# PitchshiftDelay-dsPIC_v2_3.net
KiCad netlist of a schematic drawn in EAGLE
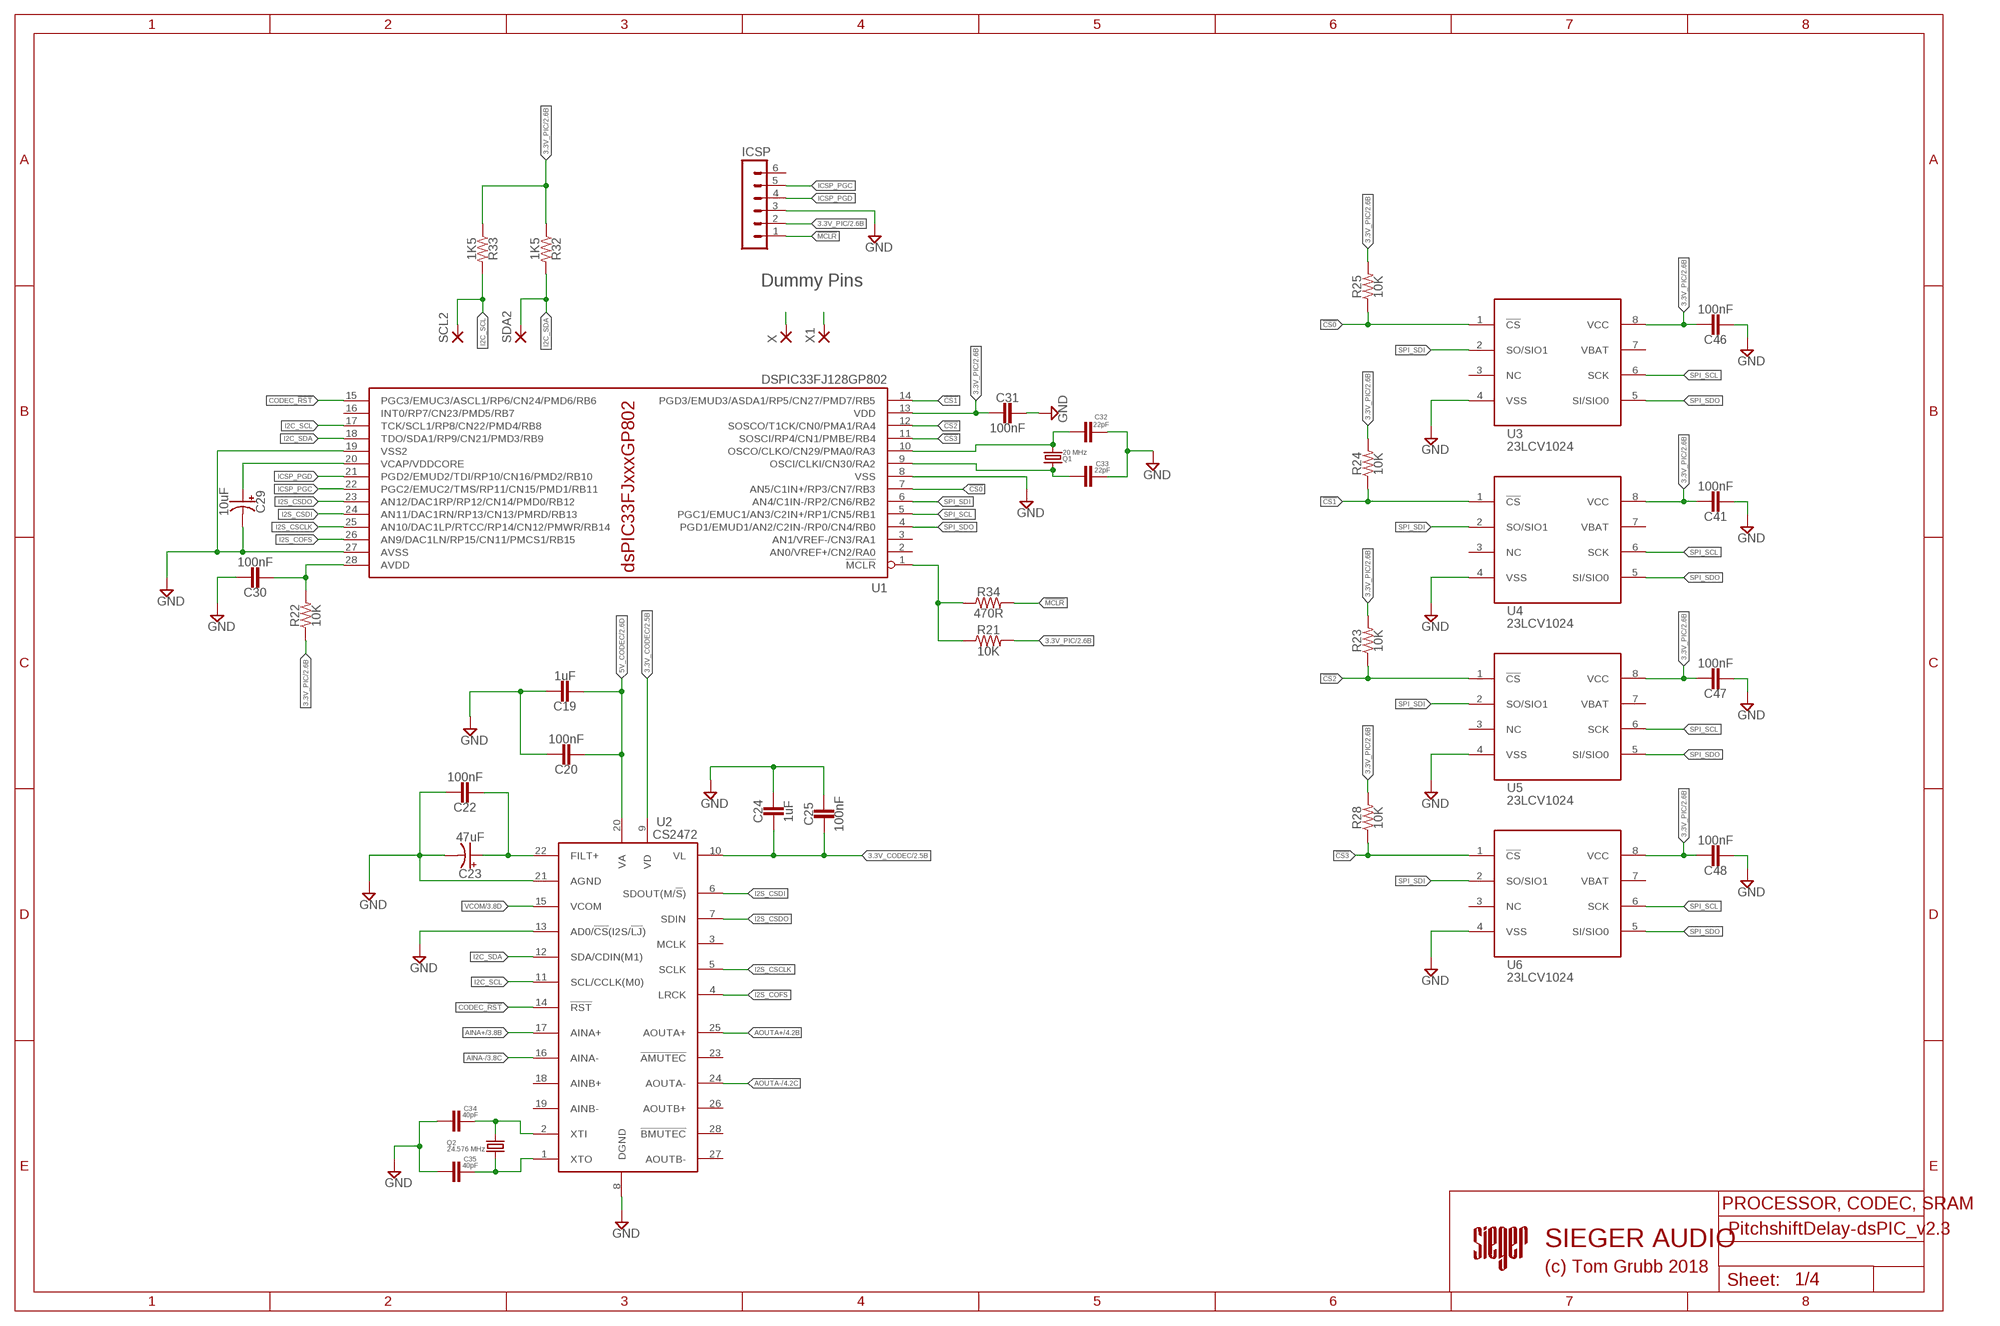
[diagram p0: schematic, sheet 1]
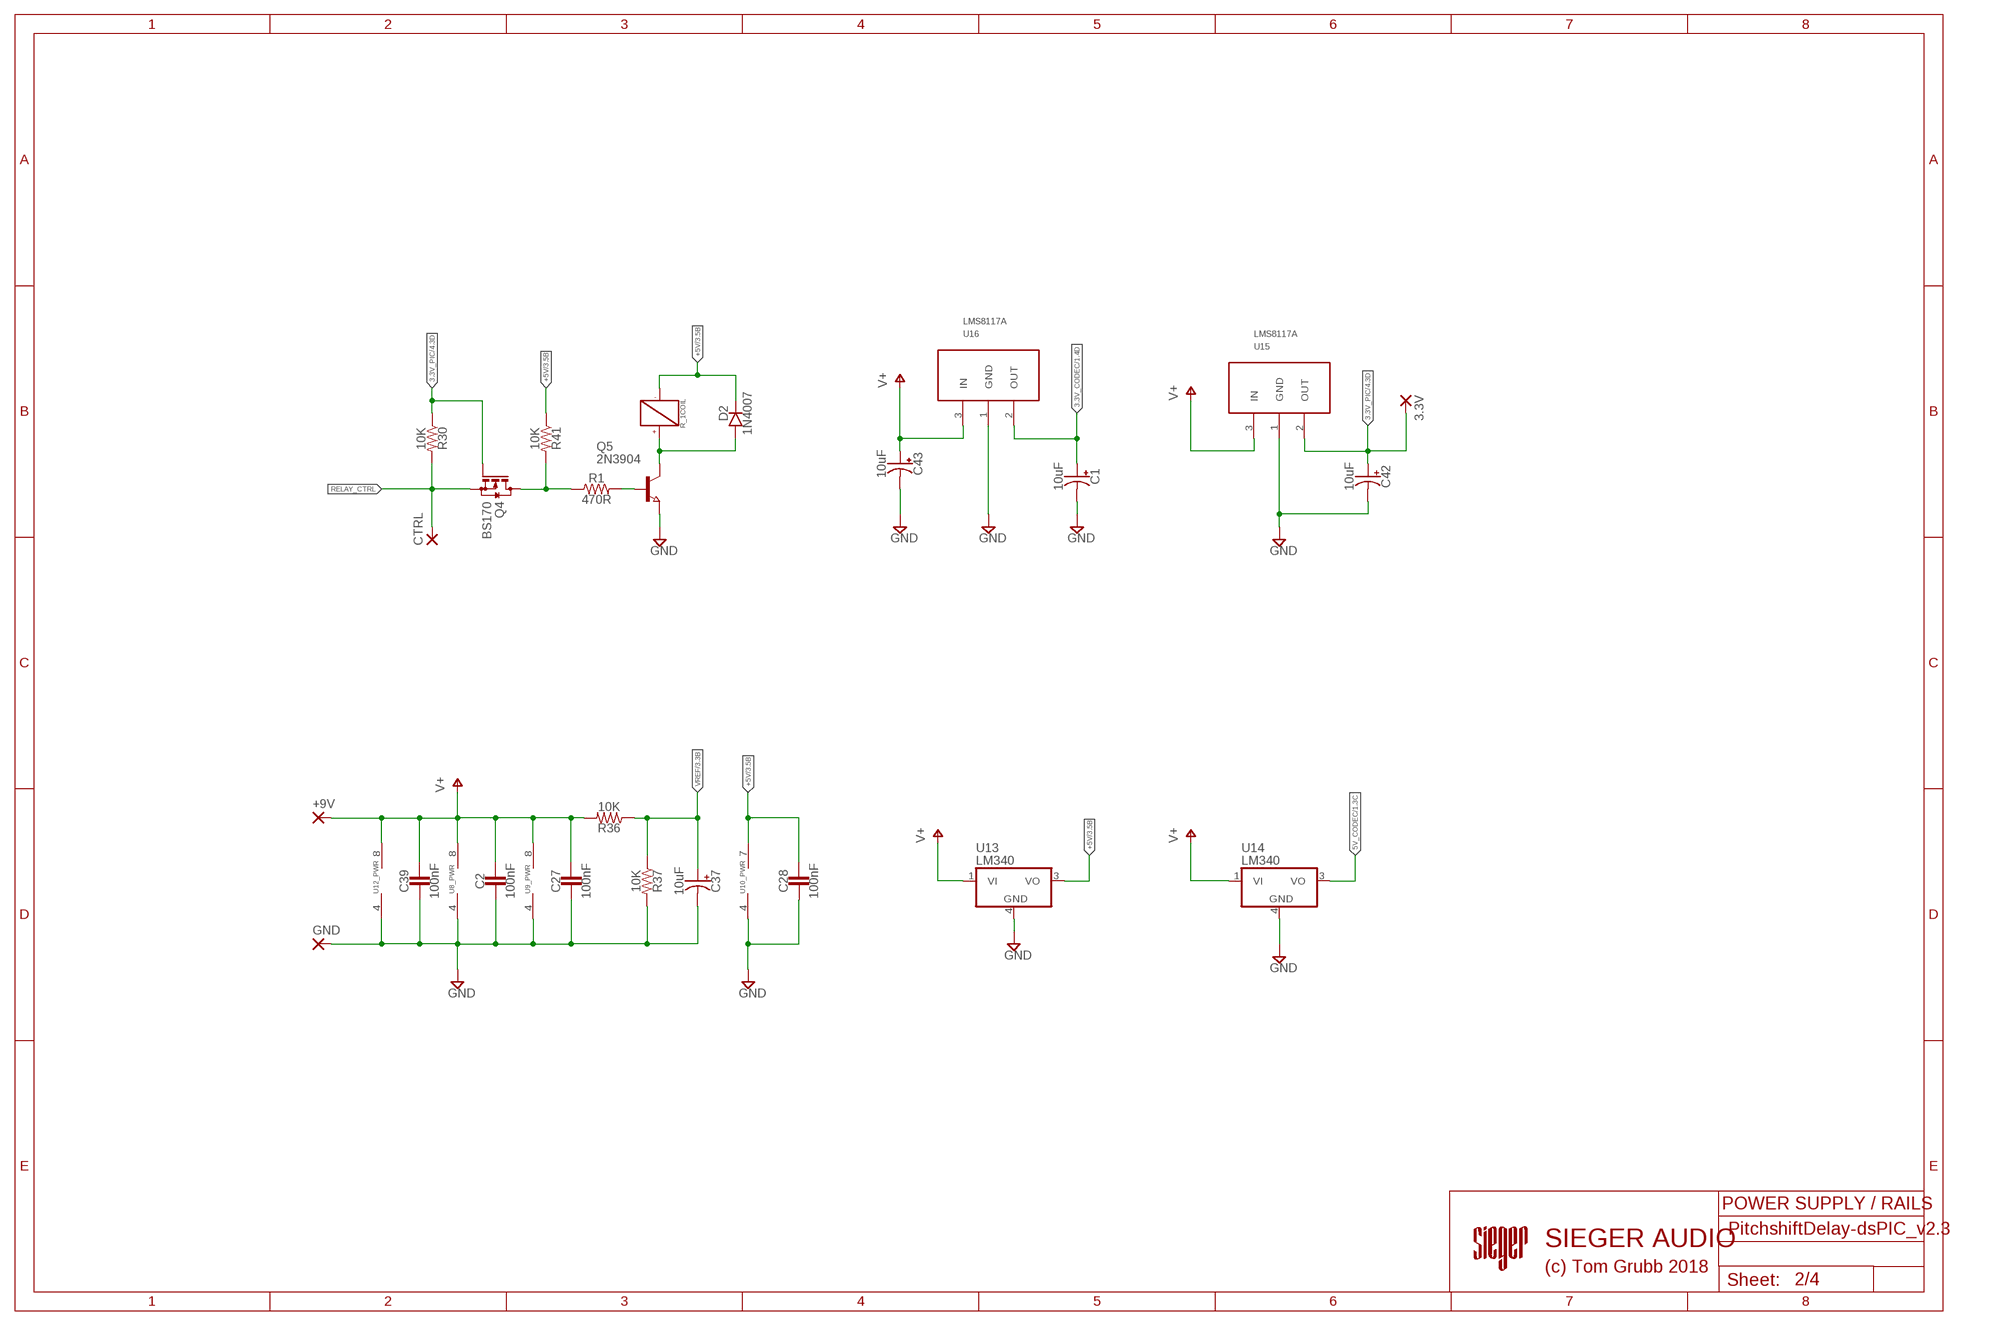
[diagram p1: schematic, sheet 2]
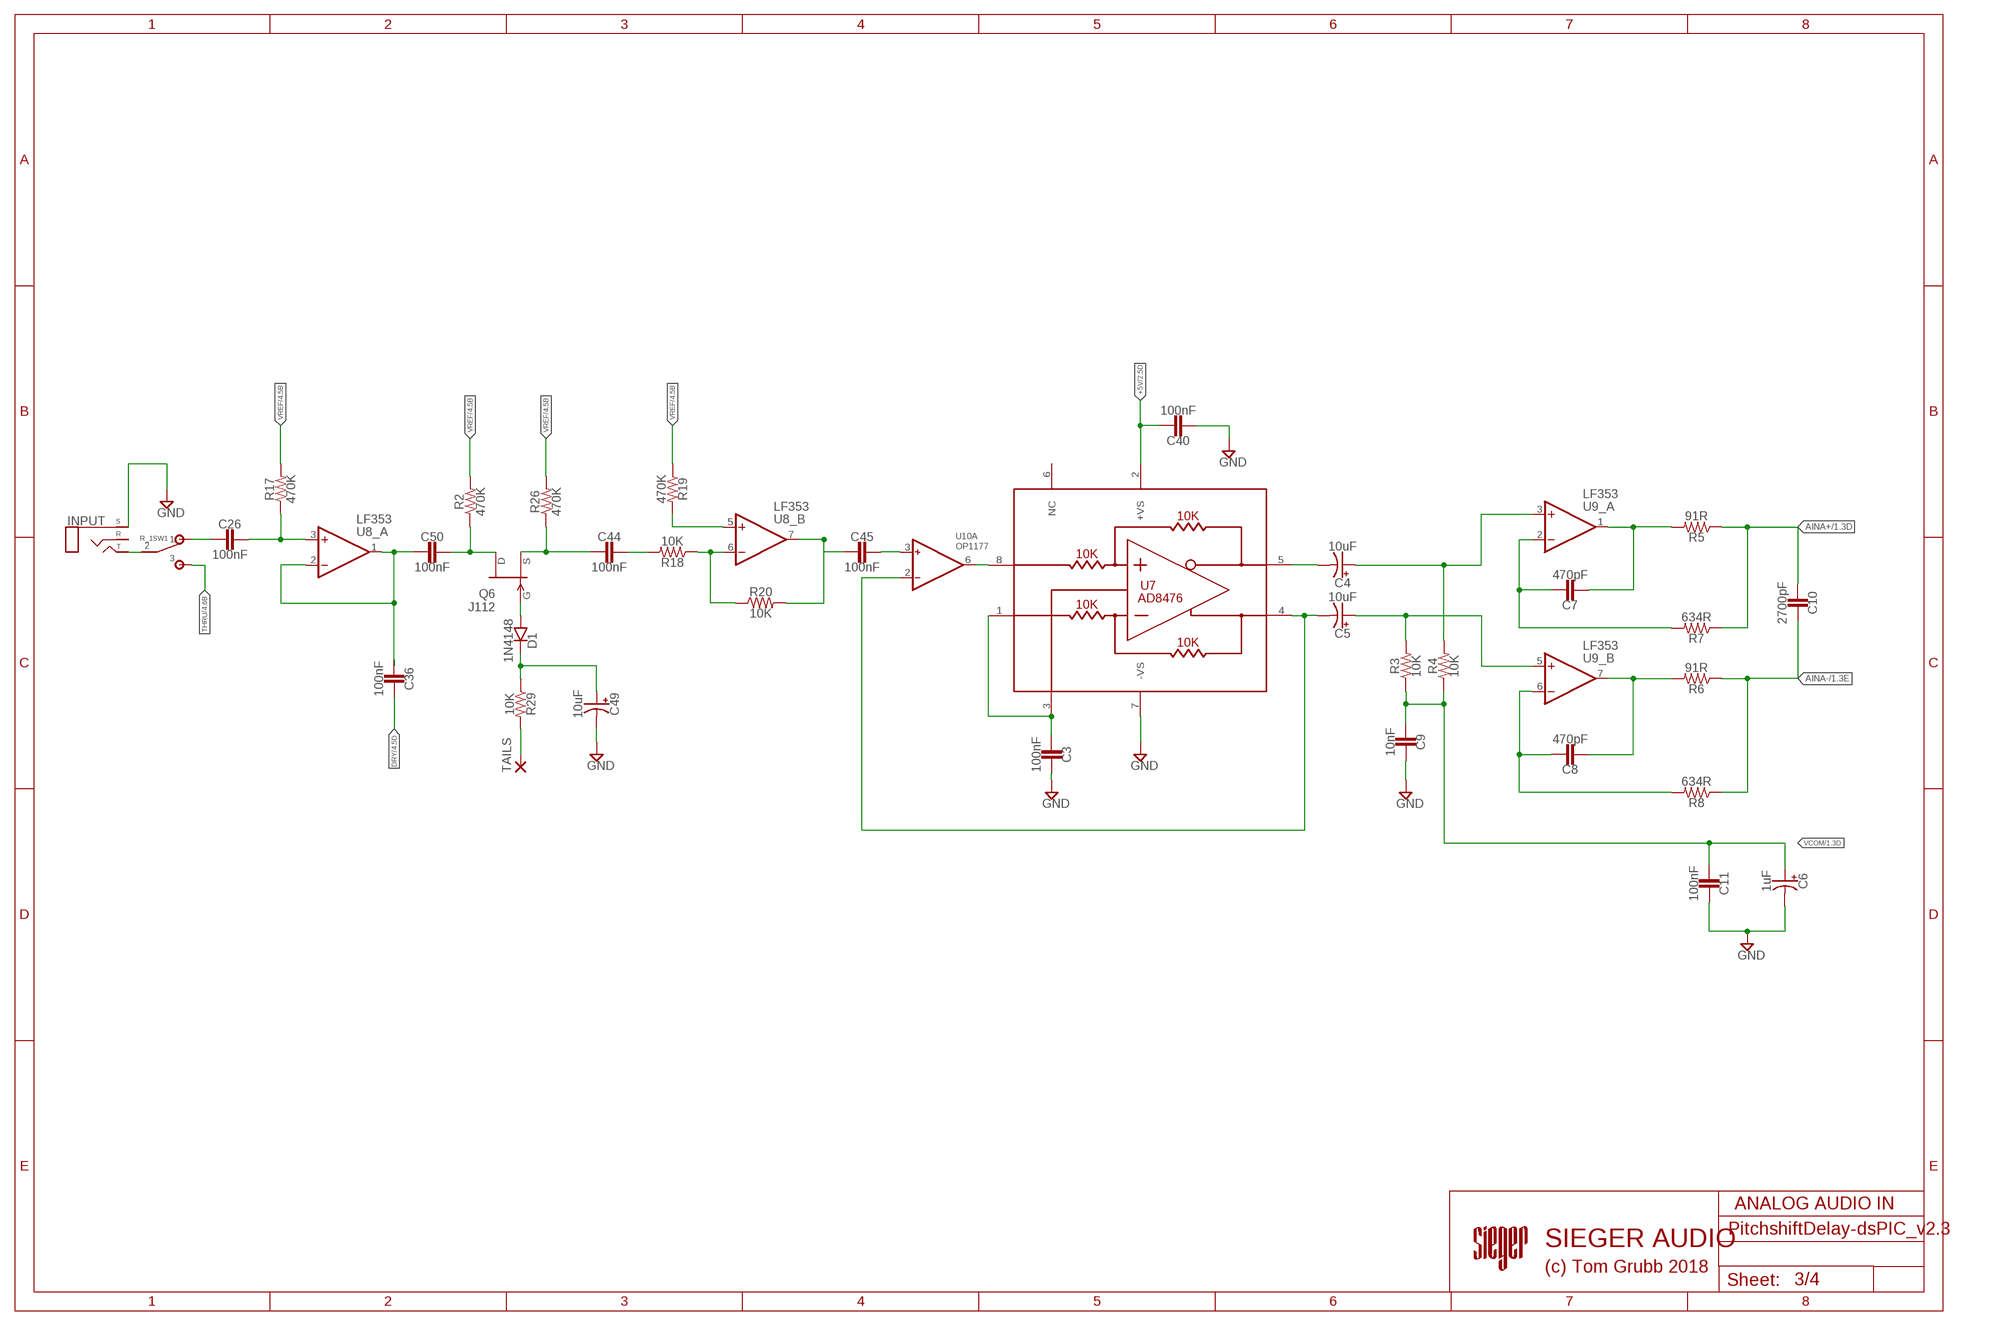
[diagram p2: schematic, sheet 3]
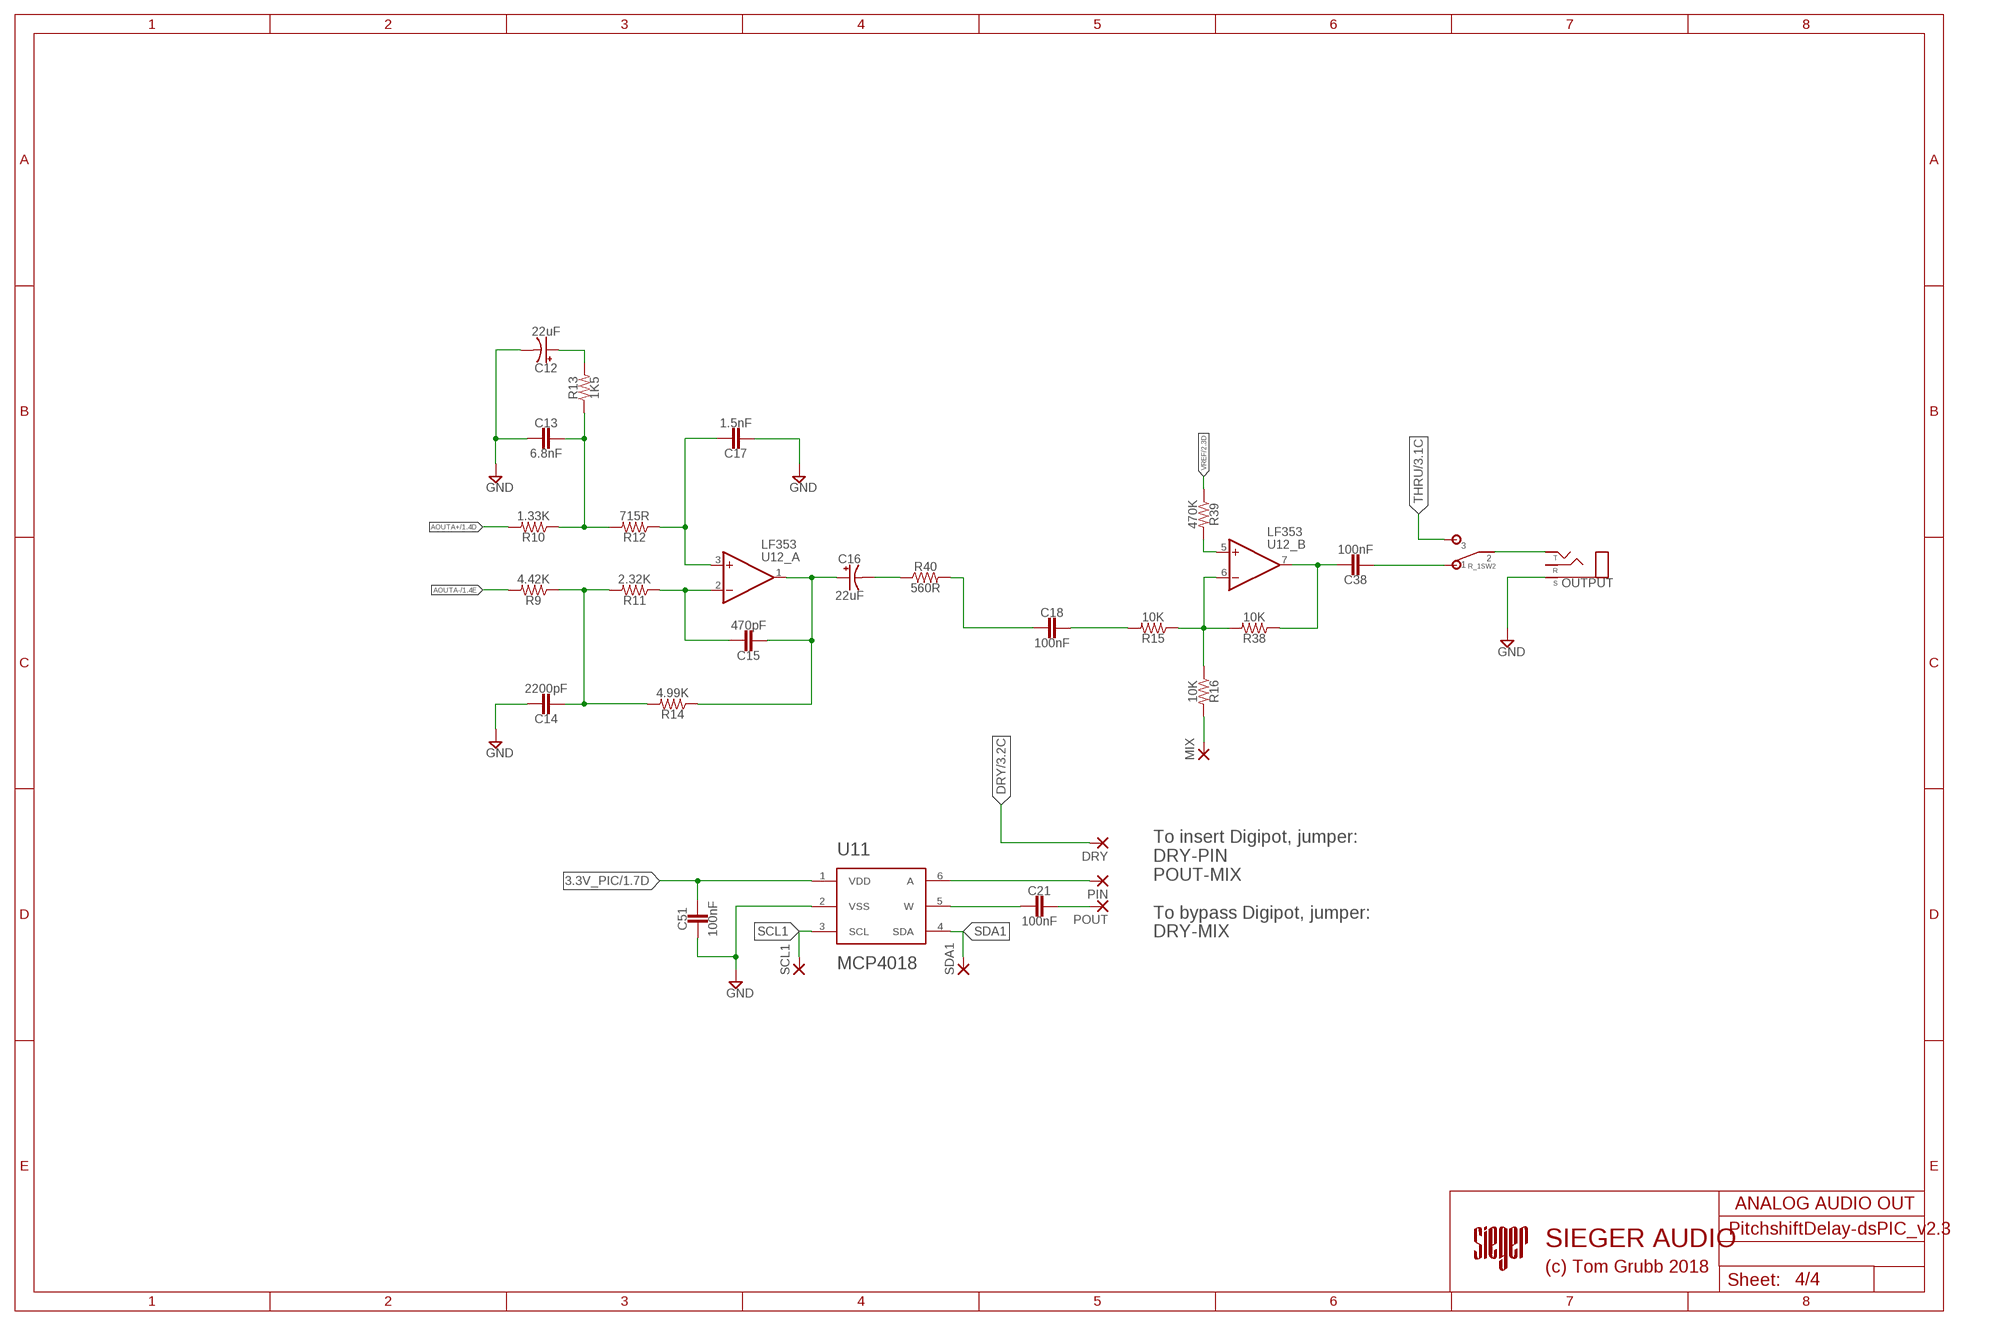
[diagram p3: schematic, sheet 4]

(export (version "E")
  (design (tool "Eeschema 10.0.6"))
  (components
    (comp (ref "C3")
      (value "100nF")
      (footprint "eagle-import:050X030_025")
      (libsource (lib "eagle-import") (part "CER/FILM1"))
    )
    (comp (ref "C4")
      (value "10uF")
      (footprint "eagle-import:050_020_1")
      (libsource (lib "eagle-import") (part "0501"))
    )
    (comp (ref "C5")
      (value "10uF")
      (footprint "eagle-import:050_020_1")
      (libsource (lib "eagle-import") (part "0501"))
    )
    (comp (ref "C6")
      (value "1uF")
      (footprint "eagle-import:050_020_1")
      (libsource (lib "eagle-import") (part "0501"))
    )
    (comp (ref "C7")
      (value "470pF")
      (footprint "eagle-import:BOX_SMALL")
      (libsource (lib "eagle-import") (part "CER/FILMBOX.1"))
    )
    (comp (ref "C8")
      (value "470pF")
      (footprint "eagle-import:BOX_SMALL")
      (libsource (lib "eagle-import") (part "CER/FILMBOX.1"))
    )
    (comp (ref "C9")
      (value "10nF")
      (footprint "eagle-import:050X030_025")
      (libsource (lib "eagle-import") (part "CER/FILM1"))
    )
    (comp (ref "C10")
      (value "2700pF")
      (footprint "eagle-import:BOX_SMALL")
      (libsource (lib "eagle-import") (part "CER/FILMBOX.1"))
    )
    (comp (ref "C11")
      (value "100nF")
      (footprint "eagle-import:050X030_025")
      (libsource (lib "eagle-import") (part "CER/FILM1"))
    )
    (comp (ref "C26")
      (value "100nF")
      (footprint "eagle-import:BOX_SMALL")
      (libsource (lib "eagle-import") (part "CER/FILMBOX.1"))
    )
    (comp (ref "C36")
      (value "100nF")
      (footprint "eagle-import:BOX_SMALL")
      (libsource (lib "eagle-import") (part "CER/FILMBOX.1"))
    )
    (comp (ref "C40")
      (value "100nF")
      (footprint "eagle-import:050X030_025")
      (libsource (lib "eagle-import") (part "CER/FILM1"))
    )
    (comp (ref "C44")
      (value "100nF")
      (footprint "eagle-import:BOX_SMALL")
      (libsource (lib "eagle-import") (part "CER/FILMBOX.1"))
    )
    (comp (ref "C45")
      (value "100nF")
      (footprint "eagle-import:BOX_SMALL")
      (libsource (lib "eagle-import") (part "CER/FILMBOX.1"))
    )
    (comp (ref "C49")
      (value "10uF")
      (footprint "eagle-import:050_020_1")
      (libsource (lib "eagle-import") (part "0501"))
    )
    (comp (ref "C50")
      (value "100nF")
      (footprint "eagle-import:BOX_SMALL")
      (libsource (lib "eagle-import") (part "CER/FILMBOX.1"))
    )
    (comp (ref "D1")
      (value "1N4148")
      (footprint "eagle-import:DO35-3")
      (libsource (lib "eagle-import") (part "DO35.3"))
    )
    (comp (ref "INPUT")
      (value "STEREO")
      (footprint "eagle-import:STEREO_PCB")
      (libsource (lib "eagle-import") (part "STEREO"))
    )
    (comp (ref "Q6")
      (value "J112")
      (footprint "eagle-import:SOT23")
      (libsource (lib "eagle-import") (part "?20SST1"))
    )
    (comp (ref "R2")
      (value "470K")
      (footprint "eagle-import:RESISTOR_C0805")
      (libsource (lib "eagle-import") (part "RESISTOR0805"))
    )
    (comp (ref "R3")
      (value "10K")
      (footprint "eagle-import:RESISTOR_C0805")
      (libsource (lib "eagle-import") (part "RESISTOR0805"))
    )
    (comp (ref "R4")
      (value "10K")
      (footprint "eagle-import:RESISTOR_C0805")
      (libsource (lib "eagle-import") (part "RESISTOR0805"))
    )
    (comp (ref "R5")
      (value "91R")
      (footprint "eagle-import:RESISTOR_C0805")
      (libsource (lib "eagle-import") (part "RESISTOR0805"))
    )
    (comp (ref "R6")
      (value "91R")
      (footprint "eagle-import:RESISTOR_C0805")
      (libsource (lib "eagle-import") (part "RESISTOR0805"))
    )
    (comp (ref "R7")
      (value "634R")
      (footprint "eagle-import:RESISTOR_C0805")
      (libsource (lib "eagle-import") (part "RESISTOR0805"))
    )
    (comp (ref "R8")
      (value "634R")
      (footprint "eagle-import:RESISTOR_C0805")
      (libsource (lib "eagle-import") (part "RESISTOR0805"))
    )
    (comp (ref "R17")
      (value "470K")
      (footprint "eagle-import:RESISTOR_C0805")
      (libsource (lib "eagle-import") (part "RESISTOR0805"))
    )
    (comp (ref "R18")
      (value "10K")
      (footprint "eagle-import:RESISTOR_C0805")
      (libsource (lib "eagle-import") (part "RESISTOR0805"))
    )
    (comp (ref "R19")
      (value "470K")
      (footprint "eagle-import:RESISTOR_C0805")
      (libsource (lib "eagle-import") (part "RESISTOR0805"))
    )
    (comp (ref "R20")
      (value "10K")
      (footprint "eagle-import:RESISTOR_C0805")
      (libsource (lib "eagle-import") (part "RESISTOR0805"))
    )
    (comp (ref "R26")
      (value "470K")
      (footprint "eagle-import:RESISTOR_C0805")
      (libsource (lib "eagle-import") (part "RESISTOR0805"))
    )
    (comp (ref "R29")
      (value "10K")
      (footprint "eagle-import:RESISTOR_C0805")
      (libsource (lib "eagle-import") (part "RESISTOR0805"))
    )
    (comp (ref "R_1")
      (value "AL5WNK_2")
      (footprint "eagle-import:10PIN")
      (libsource (lib "eagle-import") (part "AL5WNK_2"))
    )
    (comp (ref "TAILS")
      (value "2,15/1,0")
      (footprint "eagle-import:2,15_1,0")
      (libsource (lib "eagle-import") (part "2,15/1,0"))
    )
    (comp (ref "U7")
      (value "AD8476")
      (footprint "eagle-import:MSOP8")
      (libsource (lib "eagle-import") (part "AD8476"))
    )
    (comp (ref "U8")
      (value "LF353")
      (footprint "eagle-import:SO08")
      (libsource (lib "eagle-import") (part "DUALSMD"))
    )
    (comp (ref "U9")
      (value "LF353")
      (footprint "eagle-import:SO08")
      (libsource (lib "eagle-import") (part "DUALSMD"))
    )
    (comp (ref "U10")
      (value "OP1177")
      (footprint "eagle-import:MSOP8")
      (libsource (lib "eagle-import") (part "OP1177"))
    )
    (comp (ref "+9V")
      (value "2,15/1,0")
      (footprint "eagle-import:2,15_1,0")
      (libsource (lib "eagle-import") (part "2,15/1,0"))
    )
    (comp (ref "3.3V")
      (value "2,15/1,0")
      (footprint "eagle-import:2,15_1,0")
      (libsource (lib "eagle-import") (part "2,15/1,0"))
    )
    (comp (ref "C1")
      (value "10uF")
      (footprint "eagle-import:050_020_1")
      (libsource (lib "eagle-import") (part "0501"))
    )
    (comp (ref "C2")
      (value "100nF")
      (footprint "eagle-import:050X030_025")
      (libsource (lib "eagle-import") (part "CER/FILM1"))
    )
    (comp (ref "C27")
      (value "100nF")
      (footprint "eagle-import:050X030_025")
      (libsource (lib "eagle-import") (part "CER/FILM1"))
    )
    (comp (ref "C28")
      (value "100nF")
      (footprint "eagle-import:050X030_025")
      (libsource (lib "eagle-import") (part "CER/FILM1"))
    )
    (comp (ref "C37")
      (value "10uF")
      (footprint "eagle-import:050_020_1")
      (libsource (lib "eagle-import") (part "0501"))
    )
    (comp (ref "C39")
      (value "100nF")
      (footprint "eagle-import:050X030_025")
      (libsource (lib "eagle-import") (part "CER/FILM1"))
    )
    (comp (ref "C42")
      (value "10uF")
      (footprint "eagle-import:050_020_1")
      (libsource (lib "eagle-import") (part "0501"))
    )
    (comp (ref "C43")
      (value "10uF")
      (footprint "eagle-import:050_020_1")
      (libsource (lib "eagle-import") (part "0501"))
    )
    (comp (ref "CTRL")
      (value "2,15/1,0")
      (footprint "eagle-import:2,15_1,0")
      (libsource (lib "eagle-import") (part "2,15/1,0"))
    )
    (comp (ref "D2")
      (value "1N4007")
      (footprint "eagle-import:DO35-3")
      (libsource (lib "eagle-import") (part "DO35.3"))
    )
    (comp (ref "GND")
      (value "2,15/1,0")
      (footprint "eagle-import:2,15_1,0")
      (libsource (lib "eagle-import") (part "2,15/1,0"))
    )
    (comp (ref "Q4")
      (value "BS170")
      (footprint "eagle-import:SOT23")
      (libsource (lib "eagle-import") (part "BSS123"))
    )
    (comp (ref "Q5")
      (value "2N3904")
      (footprint "eagle-import:SOT23")
      (libsource (lib "eagle-import") (part "NPN-TRANSISTOR_SOT23"))
    )
    (comp (ref "R1")
      (value "470R")
      (footprint "eagle-import:RESISTOR_C0805")
      (libsource (lib "eagle-import") (part "RESISTOR0805"))
    )
    (comp (ref "R30")
      (value "10K")
      (footprint "eagle-import:RESISTOR_C0805")
      (libsource (lib "eagle-import") (part "RESISTOR0805"))
    )
    (comp (ref "R36")
      (value "10K")
      (footprint "eagle-import:RESISTOR_C0805")
      (libsource (lib "eagle-import") (part "RESISTOR0805"))
    )
    (comp (ref "R37")
      (value "10K")
      (footprint "eagle-import:RESISTOR_C0805")
      (libsource (lib "eagle-import") (part "RESISTOR0805"))
    )
    (comp (ref "R41")
      (value "10K")
      (footprint "eagle-import:RESISTOR_C0805")
      (libsource (lib "eagle-import") (part "RESISTOR0805"))
    )
    (comp (ref "U12")
      (value "LF353")
      (footprint "eagle-import:SO08")
      (libsource (lib "eagle-import") (part "DUALSMD"))
    )
    (comp (ref "U13")
      (value "LM340")
      (footprint "eagle-import:SOT223")
      (libsource (lib "eagle-import") (part "LM340?-MP05"))
    )
    (comp (ref "U14")
      (value "LM340")
      (footprint "eagle-import:SOT223")
      (libsource (lib "eagle-import") (part "LM340?-MP05"))
    )
    (comp (ref "U15")
      (value "LMS8117A")
      (footprint "eagle-import:SOT223")
      (libsource (lib "eagle-import") (part "LMS8117A"))
    )
    (comp (ref "U16")
      (value "LMS8117A")
      (footprint "eagle-import:SOT223")
      (libsource (lib "eagle-import") (part "LMS8117A"))
    )
    (comp (ref "C12")
      (value "22uF")
      (footprint "eagle-import:050_020_1")
      (libsource (lib "eagle-import") (part "0501"))
    )
    (comp (ref "C13")
      (value "6.8nF")
      (footprint "eagle-import:BOX_SMALL")
      (libsource (lib "eagle-import") (part "CER/FILMBOX.1"))
    )
    (comp (ref "C14")
      (value "2200pF")
      (footprint "eagle-import:BOX_SMALL")
      (libsource (lib "eagle-import") (part "CER/FILMBOX.1"))
    )
    (comp (ref "C15")
      (value "470pF")
      (footprint "eagle-import:BOX_SMALL")
      (libsource (lib "eagle-import") (part "CER/FILMBOX.1"))
    )
    (comp (ref "C16")
      (value "22uF")
      (footprint "eagle-import:050_020_1")
      (libsource (lib "eagle-import") (part "0501"))
    )
    (comp (ref "C17")
      (value "1.5nF")
      (footprint "eagle-import:BOX_SMALL")
      (libsource (lib "eagle-import") (part "CER/FILMBOX.1"))
    )
    (comp (ref "C18")
      (value "100nF")
      (footprint "eagle-import:BOX_SMALL")
      (libsource (lib "eagle-import") (part "CER/FILMBOX.1"))
    )
    (comp (ref "C21")
      (value "100nF")
      (footprint "eagle-import:BOX_SMALL")
      (libsource (lib "eagle-import") (part "CER/FILMBOX.1"))
    )
    (comp (ref "C38")
      (value "100nF")
      (footprint "eagle-import:BOX_SMALL")
      (libsource (lib "eagle-import") (part "CER/FILMBOX.1"))
    )
    (comp (ref "C51")
      (value "100nF")
      (footprint "eagle-import:050X030_025")
      (libsource (lib "eagle-import") (part "CER/FILM1"))
    )
    (comp (ref "DRY")
      (value "2,15/1,0")
      (footprint "eagle-import:2,15_1,0")
      (libsource (lib "eagle-import") (part "2,15/1,0"))
    )
    (comp (ref "MIX")
      (value "2,15/1,0")
      (footprint "eagle-import:2,15_1,0")
      (libsource (lib "eagle-import") (part "2,15/1,0"))
    )
    (comp (ref "OUTPUT")
      (value "STEREO")
      (footprint "eagle-import:STEREO_PCB")
      (libsource (lib "eagle-import") (part "STEREO"))
    )
    (comp (ref "PIN")
      (value "2,15/1,0")
      (footprint "eagle-import:2,15_1,0")
      (libsource (lib "eagle-import") (part "2,15/1,0"))
    )
    (comp (ref "POUT")
      (value "2,15/1,0")
      (footprint "eagle-import:2,15_1,0")
      (libsource (lib "eagle-import") (part "2,15/1,0"))
    )
    (comp (ref "R9")
      (value "4.42K")
      (footprint "eagle-import:RESISTOR_C0805")
      (libsource (lib "eagle-import") (part "RESISTOR0805"))
    )
    (comp (ref "R10")
      (value "1.33K")
      (footprint "eagle-import:RESISTOR_C0805")
      (libsource (lib "eagle-import") (part "RESISTOR0805"))
    )
    (comp (ref "R11")
      (value "2.32K")
      (footprint "eagle-import:RESISTOR_C0805")
      (libsource (lib "eagle-import") (part "RESISTOR0805"))
    )
    (comp (ref "R12")
      (value "715R")
      (footprint "eagle-import:RESISTOR_C0805")
      (libsource (lib "eagle-import") (part "RESISTOR0805"))
    )
    (comp (ref "R13")
      (value "1K5")
      (footprint "eagle-import:RESISTOR_C0805")
      (libsource (lib "eagle-import") (part "RESISTOR0805"))
    )
    (comp (ref "R14")
      (value "4.99K")
      (footprint "eagle-import:RESISTOR_C0805")
      (libsource (lib "eagle-import") (part "RESISTOR0805"))
    )
    (comp (ref "R15")
      (value "10K")
      (footprint "eagle-import:RESISTOR_C0805")
      (libsource (lib "eagle-import") (part "RESISTOR0805"))
    )
    (comp (ref "R16")
      (value "10K")
      (footprint "eagle-import:RESISTOR_C0805")
      (libsource (lib "eagle-import") (part "RESISTOR0805"))
    )
    (comp (ref "R38")
      (value "10K")
      (footprint "eagle-import:RESISTOR_C0805")
      (libsource (lib "eagle-import") (part "RESISTOR0805"))
    )
    (comp (ref "R39")
      (value "470K")
      (footprint "eagle-import:RESISTOR_C0805")
      (libsource (lib "eagle-import") (part "RESISTOR0805"))
    )
    (comp (ref "R40")
      (value "560R")
      (footprint "eagle-import:RESISTOR_C0805")
      (libsource (lib "eagle-import") (part "RESISTOR0805"))
    )
    (comp (ref "SCL1")
      (value "2,15/1,0")
      (footprint "eagle-import:2,15_1,0")
      (libsource (lib "eagle-import") (part "2,15/1,0"))
    )
    (comp (ref "SDA1")
      (value "2,15/1,0")
      (footprint "eagle-import:2,15_1,0")
      (libsource (lib "eagle-import") (part "2,15/1,0"))
    )
    (comp (ref "U11")
      (value "MCP4018")
      (footprint "eagle-import:SC70-6")
      (libsource (lib "eagle-import") (part "MCP401X"))
    )
    (comp (ref "C19")
      (value "1uF")
      (footprint "eagle-import:050X030_025")
      (libsource (lib "eagle-import") (part "CER/FILM1"))
    )
    (comp (ref "C20")
      (value "100nF")
      (footprint "eagle-import:050X030_025")
      (libsource (lib "eagle-import") (part "CER/FILM1"))
    )
    (comp (ref "C22")
      (value "100nF")
      (footprint "eagle-import:050X030_025")
      (libsource (lib "eagle-import") (part "CER/FILM1"))
    )
    (comp (ref "C23")
      (value "47uF")
      (footprint "eagle-import:050_020_1")
      (libsource (lib "eagle-import") (part "0501"))
    )
    (comp (ref "C24")
      (value "1uF")
      (footprint "eagle-import:050X030_025")
      (libsource (lib "eagle-import") (part "CER/FILM1"))
    )
    (comp (ref "C25")
      (value "100nF")
      (footprint "eagle-import:050X030_025")
      (libsource (lib "eagle-import") (part "CER/FILM1"))
    )
    (comp (ref "C29")
      (value "10uF")
      (footprint "eagle-import:050_020_1B")
      (libsource (lib "eagle-import") (part "0501B"))
    )
    (comp (ref "C30")
      (value "100nF")
      (footprint "eagle-import:050X030_025")
      (libsource (lib "eagle-import") (part "CER/FILM1"))
    )
    (comp (ref "C31")
      (value "100nF")
      (footprint "eagle-import:050X030_025")
      (libsource (lib "eagle-import") (part "CER/FILM1"))
    )
    (comp (ref "C32")
      (value "22pF")
      (footprint "eagle-import:0805")
      (libsource (lib "eagle-import") (part "CER/FILM"))
    )
    (comp (ref "C33")
      (value "22pF")
      (footprint "eagle-import:0805")
      (libsource (lib "eagle-import") (part "CER/FILM"))
    )
    (comp (ref "C34")
      (value "40pF")
      (footprint "eagle-import:0805")
      (libsource (lib "eagle-import") (part "CER/FILM"))
    )
    (comp (ref "C35")
      (value "40pF")
      (footprint "eagle-import:0805")
      (libsource (lib "eagle-import") (part "CER/FILM"))
    )
    (comp (ref "C41")
      (value "100nF")
      (footprint "eagle-import:050X030_025")
      (libsource (lib "eagle-import") (part "CER/FILM1"))
    )
    (comp (ref "C46")
      (value "100nF")
      (footprint "eagle-import:050X030_025")
      (libsource (lib "eagle-import") (part "CER/FILM1"))
    )
    (comp (ref "C47")
      (value "100nF")
      (footprint "eagle-import:050X030_025")
      (libsource (lib "eagle-import") (part "CER/FILM1"))
    )
    (comp (ref "C48")
      (value "100nF")
      (footprint "eagle-import:050X030_025")
      (libsource (lib "eagle-import") (part "CER/FILM1"))
    )
    (comp (ref "ICSP")
      (value "MA06-1")
      (footprint "eagle-import:MA06-1")
      (libsource (lib "eagle-import") (part "MA06-1"))
    )
    (comp (ref "Q1")
      (value "20 MHz")
      (footprint "eagle-import:HC49U-V")
      (libsource (lib "eagle-import") (part "CRYSTALHC49U-V"))
    )
    (comp (ref "Q2")
      (value "24.576 MHz")
      (footprint "eagle-import:HC49U-V")
      (libsource (lib "eagle-import") (part "CRYSTALHC49U-V"))
    )
    (comp (ref "R21")
      (value "10K")
      (footprint "eagle-import:RESISTOR_C0805")
      (libsource (lib "eagle-import") (part "RESISTOR0805"))
    )
    (comp (ref "R22")
      (value "10K")
      (footprint "eagle-import:RESISTOR_C0805")
      (libsource (lib "eagle-import") (part "RESISTOR0805"))
    )
    (comp (ref "R23")
      (value "10K")
      (footprint "eagle-import:RESISTOR_C0805")
      (libsource (lib "eagle-import") (part "RESISTOR0805"))
    )
    (comp (ref "R24")
      (value "10K")
      (footprint "eagle-import:RESISTOR_C0805")
      (libsource (lib "eagle-import") (part "RESISTOR0805"))
    )
    (comp (ref "R25")
      (value "10K")
      (footprint "eagle-import:RESISTOR_C0805")
      (libsource (lib "eagle-import") (part "RESISTOR0805"))
    )
    (comp (ref "R28")
      (value "10K")
      (footprint "eagle-import:RESISTOR_C0805")
      (libsource (lib "eagle-import") (part "RESISTOR0805"))
    )
    (comp (ref "R32")
      (value "1K5")
      (footprint "eagle-import:RESISTOR_C0805")
      (libsource (lib "eagle-import") (part "RESISTOR0805"))
    )
    (comp (ref "R33")
      (value "1K5")
      (footprint "eagle-import:RESISTOR_C0805")
      (libsource (lib "eagle-import") (part "RESISTOR0805"))
    )
    (comp (ref "R34")
      (value "470R")
      (footprint "eagle-import:RESISTOR_C0805")
      (libsource (lib "eagle-import") (part "RESISTOR0805"))
    )
    (comp (ref "SCL2")
      (value "2,15/1,0")
      (footprint "eagle-import:2,15_1,0")
      (libsource (lib "eagle-import") (part "2,15/1,0"))
    )
    (comp (ref "SDA2")
      (value "2,15/1,0")
      (footprint "eagle-import:2,15_1,0")
      (libsource (lib "eagle-import") (part "2,15/1,0"))
    )
    (comp (ref "U1")
      (value "DSPIC33FJ128GP802")
      (footprint "eagle-import:SO28W")
      (libsource (lib "eagle-import") (part "DSPIC33FJXXXGP802SMT"))
    )
    (comp (ref "U2")
      (value "CS2472")
      (footprint "eagle-import:TSSOP28L")
      (libsource (lib "eagle-import") (part "CS2472"))
    )
    (comp (ref "U3")
      (value "23LCV1024")
      (footprint "eagle-import:SOIC8")
      (libsource (lib "eagle-import") (part "23LCV1024"))
    )
    (comp (ref "U4")
      (value "23LCV1024")
      (footprint "eagle-import:SOIC8")
      (libsource (lib "eagle-import") (part "23LCV1024"))
    )
    (comp (ref "U5")
      (value "23LCV1024")
      (footprint "eagle-import:SOIC8")
      (libsource (lib "eagle-import") (part "23LCV1024"))
    )
    (comp (ref "U6")
      (value "23LCV1024")
      (footprint "eagle-import:SOIC8")
      (libsource (lib "eagle-import") (part "23LCV1024"))
    )
    (comp (ref "X")
      (value "2,15/1,0")
      (footprint "eagle-import:2,15_1,0")
      (libsource (lib "eagle-import") (part "2,15/1,0"))
    )
    (comp (ref "X1")
      (value "2,15/1,0")
      (footprint "eagle-import:2,15_1,0")
      (libsource (lib "eagle-import") (part "2,15/1,0"))
    )
  )
  (nets
    (net (code "1") (name "+5V") (class "Default")
      (node (ref "C28") (pin "1") (pinfunction "1_1") (pintype "passive"))
      (node (ref "C40") (pin "1") (pinfunction "1_1") (pintype "passive"))
      (node (ref "D2") (pin "C") (pinfunction "C_C") (pintype "passive"))
      (node (ref "R41") (pin "1") (pinfunction "1_1") (pintype "passive"))
      (node (ref "R_1") (pin "P$10") (pinfunction "-_P$10") (pintype "bidirectional"))
      (node (ref "U10") (pin "7") (pinfunction "V+_7") (pintype "power_in"))
      (node (ref "U13") (pin "3") (pinfunction "VO_3") (pintype "passive"))
      (node (ref "U7") (pin "2") (pinfunction "+VS_2") (pintype "power_in"))
    )
    (net (code "2") (name "3.3V_CODEC") (class "Default")
      (node (ref "C1") (pin "+") (pinfunction "+_+") (pintype "passive"))
      (node (ref "C24") (pin "2") (pinfunction "2_2") (pintype "passive"))
      (node (ref "C25") (pin "2") (pinfunction "2_2") (pintype "passive"))
      (node (ref "U16") (pin "2") (pinfunction "OUT_2") (pintype "bidirectional"))
      (node (ref "U2") (pin "10") (pinfunction "VL_10") (pintype "bidirectional"))
      (node (ref "U2") (pin "9") (pinfunction "VD_9") (pintype "bidirectional"))
    )
    (net (code "3") (name "3.3V_PIC") (class "Default")
      (node (ref "3.3V") (pin "1") (pinfunction "P_1") (pintype "passive"))
      (node (ref "C31") (pin "2") (pinfunction "2_2") (pintype "passive"))
      (node (ref "C41") (pin "1") (pinfunction "1_1") (pintype "passive"))
      (node (ref "C42") (pin "+") (pinfunction "+_+") (pintype "passive"))
      (node (ref "C46") (pin "1") (pinfunction "1_1") (pintype "passive"))
      (node (ref "C47") (pin "1") (pinfunction "1_1") (pintype "passive"))
      (node (ref "C48") (pin "1") (pinfunction "1_1") (pintype "passive"))
      (node (ref "C51") (pin "1") (pinfunction "1_1") (pintype "passive"))
      (node (ref "ICSP") (pin "2") (pinfunction "2_2") (pintype "passive"))
      (node (ref "Q4") (pin "1") (pinfunction "G_1") (pintype "passive"))
      (node (ref "R21") (pin "2") (pinfunction "2_2") (pintype "passive"))
      (node (ref "R22") (pin "1") (pinfunction "1_1") (pintype "passive"))
      (node (ref "R23") (pin "2") (pinfunction "2_2") (pintype "passive"))
      (node (ref "R24") (pin "2") (pinfunction "2_2") (pintype "passive"))
      (node (ref "R25") (pin "2") (pinfunction "2_2") (pintype "passive"))
      (node (ref "R28") (pin "2") (pinfunction "2_2") (pintype "passive"))
      (node (ref "R30") (pin "1") (pinfunction "1_1") (pintype "passive"))
      (node (ref "R32") (pin "1") (pinfunction "1_1") (pintype "passive"))
      (node (ref "R33") (pin "1") (pinfunction "1_1") (pintype "passive"))
      (node (ref "U1") (pin "13") (pinfunction "VDD_13") (pintype "power_in"))
      (node (ref "U11") (pin "1") (pinfunction "VDD_1") (pintype "bidirectional"))
      (node (ref "U15") (pin "2") (pinfunction "OUT_2") (pintype "bidirectional"))
      (node (ref "U3") (pin "8") (pinfunction "VCC_8") (pintype "bidirectional"))
      (node (ref "U4") (pin "8") (pinfunction "VCC_8") (pintype "bidirectional"))
      (node (ref "U5") (pin "8") (pinfunction "VCC_8") (pintype "bidirectional"))
      (node (ref "U6") (pin "8") (pinfunction "VCC_8") (pintype "bidirectional"))
    )
    (net (code "4") (name "5V_CODEC") (class "Default")
      (node (ref "C19") (pin "2") (pinfunction "2_2") (pintype "passive"))
      (node (ref "C20") (pin "2") (pinfunction "2_2") (pintype "passive"))
      (node (ref "U14") (pin "3") (pinfunction "VO_3") (pintype "passive"))
      (node (ref "U2") (pin "20") (pinfunction "VA_20") (pintype "bidirectional"))
    )
    (net (code "5") (name "AINA+") (class "Default")
      (node (ref "C10") (pin "2") (pinfunction "2_2") (pintype "passive"))
      (node (ref "R5") (pin "1") (pinfunction "1_1") (pintype "passive"))
      (node (ref "R7") (pin "1") (pinfunction "1_1") (pintype "passive"))
      (node (ref "U2") (pin "17") (pinfunction "AINA+_17") (pintype "bidirectional"))
    )
    (net (code "6") (name "AINA-") (class "Default")
      (node (ref "C10") (pin "1") (pinfunction "1_1") (pintype "passive"))
      (node (ref "R6") (pin "1") (pinfunction "1_1") (pintype "passive"))
      (node (ref "R8") (pin "1") (pinfunction "1_1") (pintype "passive"))
      (node (ref "U2") (pin "16") (pinfunction "AINA-_16") (pintype "bidirectional"))
    )
    (net (code "7") (name "AOUTA+") (class "Default")
      (node (ref "R10") (pin "2") (pinfunction "2_2") (pintype "passive"))
      (node (ref "U2") (pin "25") (pinfunction "AOUTA+_25") (pintype "bidirectional"))
    )
    (net (code "8") (name "AOUTA-") (class "Default")
      (node (ref "R9") (pin "2") (pinfunction "2_2") (pintype "passive"))
      (node (ref "U2") (pin "24") (pinfunction "AOUTA-_24") (pintype "bidirectional"))
    )
    (net (code "9") (name "CODEC_~{RST}") (class "Default")
      (node (ref "U1") (pin "15") (pinfunction "PGC3/EMUC3/ASCL1/RP6/CN24/PMD6/RB6_15") (pintype "bidirectional"))
      (node (ref "U2") (pin "14") (pinfunction "~{RST}_14") (pintype "bidirectional"))
    )
    (net (code "10") (name "DRY") (class "Default")
      (node (ref "C36") (pin "1") (pinfunction "1_1") (pintype "passive"))
      (node (ref "DRY") (pin "1") (pinfunction "P_1") (pintype "passive"))
    )
    (net (code "11") (name "GND") (class "Default")
      (node (ref "C1") (pin "-") (pinfunction "-_-") (pintype "passive"))
      (node (ref "C11") (pin "1") (pinfunction "1_1") (pintype "passive"))
      (node (ref "C12") (pin "-") (pinfunction "-_-") (pintype "passive"))
      (node (ref "C13") (pin "2") (pinfunction "2_2") (pintype "passive"))
      (node (ref "C14") (pin "1") (pinfunction "1_1") (pintype "passive"))
      (node (ref "C17") (pin "2") (pinfunction "2_2") (pintype "passive"))
      (node (ref "C19") (pin "1") (pinfunction "1_1") (pintype "passive"))
      (node (ref "C2") (pin "2") (pinfunction "2_2") (pintype "passive"))
      (node (ref "C20") (pin "1") (pinfunction "1_1") (pintype "passive"))
      (node (ref "C22") (pin "1") (pinfunction "1_1") (pintype "passive"))
      (node (ref "C23") (pin "-") (pinfunction "-_-") (pintype "passive"))
      (node (ref "C24") (pin "1") (pinfunction "1_1") (pintype "passive"))
      (node (ref "C25") (pin "1") (pinfunction "1_1") (pintype "passive"))
      (node (ref "C27") (pin "2") (pinfunction "2_2") (pintype "passive"))
      (node (ref "C28") (pin "2") (pinfunction "2_2") (pintype "passive"))
      (node (ref "C29") (pin "-") (pinfunction "-_-") (pintype "passive"))
      (node (ref "C3") (pin "1") (pinfunction "1_1") (pintype "passive"))
      (node (ref "C30") (pin "1") (pinfunction "1_1") (pintype "passive"))
      (node (ref "C31") (pin "1") (pinfunction "1_1") (pintype "passive"))
      (node (ref "C32") (pin "1") (pinfunction "1_1") (pintype "passive"))
      (node (ref "C33") (pin "1") (pinfunction "1_1") (pintype "passive"))
      (node (ref "C34") (pin "2") (pinfunction "2_2") (pintype "passive"))
      (node (ref "C35") (pin "2") (pinfunction "2_2") (pintype "passive"))
      (node (ref "C37") (pin "-") (pinfunction "-_-") (pintype "passive"))
      (node (ref "C39") (pin "2") (pinfunction "2_2") (pintype "passive"))
      (node (ref "C40") (pin "2") (pinfunction "2_2") (pintype "passive"))
      (node (ref "C41") (pin "2") (pinfunction "2_2") (pintype "passive"))
      (node (ref "C42") (pin "-") (pinfunction "-_-") (pintype "passive"))
      (node (ref "C43") (pin "-") (pinfunction "-_-") (pintype "passive"))
      (node (ref "C46") (pin "2") (pinfunction "2_2") (pintype "passive"))
      (node (ref "C47") (pin "2") (pinfunction "2_2") (pintype "passive"))
      (node (ref "C48") (pin "2") (pinfunction "2_2") (pintype "passive"))
      (node (ref "C49") (pin "-") (pinfunction "-_-") (pintype "passive"))
      (node (ref "C51") (pin "2") (pinfunction "2_2") (pintype "passive"))
      (node (ref "C6") (pin "-") (pinfunction "-_-") (pintype "passive"))
      (node (ref "C9") (pin "1") (pinfunction "1_1") (pintype "passive"))
      (node (ref "GND") (pin "1") (pinfunction "P_1") (pintype "passive"))
      (node (ref "ICSP") (pin "3") (pinfunction "3_3") (pintype "passive"))
      (node (ref "INPUT") (pin "P$1") (pinfunction "S_P$1") (pintype "passive"))
      (node (ref "OUTPUT") (pin "P$1") (pinfunction "S_P$1") (pintype "passive"))
      (node (ref "Q5") (pin "2") (pinfunction "E_2") (pintype "passive"))
      (node (ref "R37") (pin "2") (pinfunction "2_2") (pintype "passive"))
      (node (ref "U1") (pin "19") (pinfunction "VSS2_19") (pintype "power_in"))
      (node (ref "U1") (pin "27") (pinfunction "AVSS_27") (pintype "power_in"))
      (node (ref "U1") (pin "8") (pinfunction "VSS_8") (pintype "power_in"))
      (node (ref "U10") (pin "4") (pinfunction "V-_4") (pintype "power_in"))
      (node (ref "U11") (pin "2") (pinfunction "VSS_2") (pintype "bidirectional"))
      (node (ref "U12") (pin "4") (pinfunction "V-_4") (pintype "power_in"))
      (node (ref "U13") (pin "4") (pinfunction "GND_4") (pintype "passive"))
      (node (ref "U14") (pin "4") (pinfunction "GND_4") (pintype "passive"))
      (node (ref "U15") (pin "1") (pinfunction "GND_1") (pintype "bidirectional"))
      (node (ref "U16") (pin "1") (pinfunction "GND_1") (pintype "bidirectional"))
      (node (ref "U2") (pin "13") (pinfunction "AD0/~{CS}(I2S/~{LJ})_13") (pintype "bidirectional"))
      (node (ref "U2") (pin "21") (pinfunction "AGND_21") (pintype "bidirectional"))
      (node (ref "U2") (pin "8") (pinfunction "DGND_8") (pintype "bidirectional"))
      (node (ref "U3") (pin "4") (pinfunction "VSS_4") (pintype "bidirectional"))
      (node (ref "U4") (pin "4") (pinfunction "VSS_4") (pintype "bidirectional"))
      (node (ref "U5") (pin "4") (pinfunction "VSS_4") (pintype "bidirectional"))
      (node (ref "U6") (pin "4") (pinfunction "VSS_4") (pintype "bidirectional"))
      (node (ref "U7") (pin "7") (pinfunction "-VS_7") (pintype "power_in"))
      (node (ref "U8") (pin "4") (pinfunction "V-_4") (pintype "power_in"))
      (node (ref "U9") (pin "4") (pinfunction "V-_4") (pintype "power_in"))
    )
    (net (code "12") (name "I2C_SCL") (class "Default")
      (node (ref "R33") (pin "2") (pinfunction "2_2") (pintype "passive"))
      (node (ref "SCL2") (pin "1") (pinfunction "P_1") (pintype "passive"))
      (node (ref "U1") (pin "17") (pinfunction "TCK/SCL1/RP8/CN22/PMD4/RB8_17") (pintype "bidirectional"))
      (node (ref "U2") (pin "11") (pinfunction "SCL/CCLK(M0)_11") (pintype "bidirectional"))
      (node (ref "X") (pin "1") (pinfunction "P_1") (pintype "passive"))
    )
    (net (code "13") (name "I2C_SDA") (class "Default")
      (node (ref "R32") (pin "2") (pinfunction "2_2") (pintype "passive"))
      (node (ref "SDA2") (pin "1") (pinfunction "P_1") (pintype "passive"))
      (node (ref "U1") (pin "18") (pinfunction "TDO/SDA1/RP9/CN21/PMD3/RB9_18") (pintype "bidirectional"))
      (node (ref "U2") (pin "12") (pinfunction "SDA/CDIN(M1)_12") (pintype "bidirectional"))
    )
    (net (code "14") (name "I2S_COFS") (class "Default")
      (node (ref "U1") (pin "26") (pinfunction "AN9/DAC1LN/RP15/CN11/PMCS1/RB15_26") (pintype "bidirectional"))
      (node (ref "U2") (pin "4") (pinfunction "LRCK_4") (pintype "bidirectional"))
    )
    (net (code "15") (name "I2S_CSCLK") (class "Default")
      (node (ref "U1") (pin "25") (pinfunction "AN10/DAC1LP/RTCC/RP14/CN12/PMWR/RB14_25") (pintype "bidirectional"))
      (node (ref "U2") (pin "5") (pinfunction "SCLK_5") (pintype "bidirectional"))
    )
    (net (code "16") (name "I2S_CSDI") (class "Default")
      (node (ref "U1") (pin "24") (pinfunction "AN11/DAC1RN/RP13/CN13/PMRD/RB13_24") (pintype "bidirectional"))
      (node (ref "U2") (pin "6") (pinfunction "SDOUT(M/~{S})_6") (pintype "bidirectional"))
    )
    (net (code "17") (name "I2S_CSDO") (class "Default")
      (node (ref "U1") (pin "23") (pinfunction "AN12/DAC1RP/RP12/CN14/PMD0/RB12_23") (pintype "bidirectional"))
      (node (ref "U2") (pin "7") (pinfunction "SDIN_7") (pintype "bidirectional"))
    )
    (net (code "18") (name "ICSP_PGC") (class "Default")
      (node (ref "ICSP") (pin "5") (pinfunction "5_5") (pintype "passive"))
      (node (ref "U1") (pin "22") (pinfunction "PGC2/EMUC2/TMS/RP11/CN15/PMD1/RB11_22") (pintype "bidirectional"))
    )
    (net (code "19") (name "ICSP_PGD") (class "Default")
      (node (ref "ICSP") (pin "4") (pinfunction "4_4") (pintype "passive"))
      (node (ref "U1") (pin "21") (pinfunction "PGD2/EMUD2/TDI/RP10/CN16/PMD2/RB10_21") (pintype "bidirectional"))
    )
    (net (code "20") (name "Net-(C12-Pad+)") (class "Default")
      (node (ref "C12") (pin "+") (pinfunction "+_+") (pintype "passive"))
      (node (ref "R13") (pin "2") (pinfunction "2_2") (pintype "passive"))
    )
    (net (code "21") (name "Net-(C13-Pad1)") (class "Default")
      (node (ref "C13") (pin "1") (pinfunction "1_1") (pintype "passive"))
      (node (ref "R10") (pin "1") (pinfunction "1_1") (pintype "passive"))
      (node (ref "R12") (pin "2") (pinfunction "2_2") (pintype "passive"))
      (node (ref "R13") (pin "1") (pinfunction "1_1") (pintype "passive"))
    )
    (net (code "22") (name "Net-(C14-Pad2)") (class "Default")
      (node (ref "C14") (pin "2") (pinfunction "2_2") (pintype "passive"))
      (node (ref "R11") (pin "2") (pinfunction "2_2") (pintype "passive"))
      (node (ref "R14") (pin "2") (pinfunction "2_2") (pintype "passive"))
      (node (ref "R9") (pin "1") (pinfunction "1_1") (pintype "passive"))
    )
    (net (code "23") (name "Net-(C16-Pad-)") (class "Default")
      (node (ref "C16") (pin "-") (pinfunction "-_-") (pintype "passive"))
      (node (ref "R40") (pin "1") (pinfunction "1_1") (pintype "passive"))
    )
    (net (code "24") (name "Net-(C18-Pad1)") (class "Default")
      (node (ref "C18") (pin "1") (pinfunction "1_1") (pintype "passive"))
      (node (ref "R15") (pin "2") (pinfunction "2_2") (pintype "passive"))
    )
    (net (code "25") (name "Net-(C18-Pad2)") (class "Default")
      (node (ref "C18") (pin "2") (pinfunction "2_2") (pintype "passive"))
      (node (ref "R40") (pin "2") (pinfunction "2_2") (pintype "passive"))
    )
    (net (code "26") (name "Net-(C44-Pad1)") (class "Default")
      (node (ref "C44") (pin "1") (pinfunction "1_1") (pintype "passive"))
      (node (ref "R18") (pin "2") (pinfunction "2_2") (pintype "passive"))
    )
    (net (code "27") (name "Net-(C49-Pad+)") (class "Default")
      (node (ref "C49") (pin "+") (pinfunction "+_+") (pintype "passive"))
      (node (ref "D1") (pin "C") (pinfunction "C_C") (pintype "passive"))
      (node (ref "R29") (pin "1") (pinfunction "1_1") (pintype "passive"))
    )
    (net (code "28") (name "Net-(INPUT-T)") (class "Default")
      (node (ref "INPUT") (pin "P$3") (pinfunction "T_P$3") (pintype "passive"))
      (node (ref "R_1") (pin "P$3") (pinfunction "2_P$3") (pintype "passive"))
    )
    (net (code "29") (name "Net-(MIX-P)") (class "Default")
      (node (ref "MIX") (pin "1") (pinfunction "P_1") (pintype "passive"))
      (node (ref "R16") (pin "2") (pinfunction "2_2") (pintype "passive"))
    )
    (net (code "30") (name "Net-(OUTPUT-T)") (class "Default")
      (node (ref "OUTPUT") (pin "P$3") (pinfunction "T_P$3") (pintype "passive"))
      (node (ref "R_1") (pin "P$8") (pinfunction "2_P$8") (pintype "passive"))
    )
    (net (code "31") (name "Net-(PIN-P)") (class "Default")
      (node (ref "PIN") (pin "1") (pinfunction "P_1") (pintype "passive"))
      (node (ref "U11") (pin "6") (pinfunction "A_6") (pintype "bidirectional"))
    )
    (net (code "32") (name "Net-(POUT-P)") (class "Default")
      (node (ref "C21") (pin "1") (pinfunction "1_1") (pintype "passive"))
      (node (ref "POUT") (pin "1") (pinfunction "P_1") (pintype "passive"))
    )
    (net (code "33") (name "Net-(Q4-D)") (class "Default")
      (node (ref "Q4") (pin "3") (pinfunction "D_3") (pintype "passive"))
      (node (ref "R1") (pin "1") (pinfunction "1_1") (pintype "passive"))
      (node (ref "R41") (pin "2") (pinfunction "2_2") (pintype "passive"))
    )
    (net (code "34") (name "Net-(Q5-B)") (class "Default")
      (node (ref "Q5") (pin "1") (pinfunction "B_1") (pintype "passive"))
      (node (ref "R1") (pin "2") (pinfunction "2_2") (pintype "passive"))
    )
    (net (code "35") (name "Net-(Q5-C)") (class "Default")
      (node (ref "D2") (pin "A") (pinfunction "A_A") (pintype "passive"))
      (node (ref "Q5") (pin "3") (pinfunction "C_3") (pintype "passive"))
      (node (ref "R_1") (pin "P$1") (pinfunction "+_P$1") (pintype "bidirectional"))
    )
    (net (code "36") (name "Net-(Q6-D)") (class "Default")
      (node (ref "C50") (pin "1") (pinfunction "1_1") (pintype "passive"))
      (node (ref "Q6") (pin "1") (pinfunction "D_1") (pintype "passive"))
      (node (ref "R2") (pin "1") (pinfunction "1_1") (pintype "passive"))
    )
    (net (code "37") (name "Net-(Q6-G)") (class "Default")
      (node (ref "D1") (pin "A") (pinfunction "A_A") (pintype "passive"))
      (node (ref "Q6") (pin "3") (pinfunction "G_3") (pintype "passive"))
    )
    (net (code "38") (name "Net-(Q6-S)") (class "Default")
      (node (ref "C44") (pin "2") (pinfunction "2_2") (pintype "passive"))
      (node (ref "Q6") (pin "2") (pinfunction "S_2") (pintype "passive"))
      (node (ref "R26") (pin "1") (pinfunction "1_1") (pintype "passive"))
    )
    (net (code "39") (name "Net-(R_1B-1)") (class "Default")
      (node (ref "C26") (pin "2") (pinfunction "2_2") (pintype "passive"))
      (node (ref "R_1") (pin "P$2") (pinfunction "1_P$2") (pintype "passive"))
    )
    (net (code "40") (name "Net-(R_1C-1)") (class "Default")
      (node (ref "C38") (pin "2") (pinfunction "2_2") (pintype "passive"))
      (node (ref "R_1") (pin "P$9") (pinfunction "1_P$9") (pintype "passive"))
    )
    (net (code "41") (name "Net-(TAILS-P)") (class "Default")
      (node (ref "R29") (pin "2") (pinfunction "2_2") (pintype "passive"))
      (node (ref "TAILS") (pin "1") (pinfunction "P_1") (pintype "passive"))
    )
    (net (code "42") (name "Net-(U1-AVDD)") (class "Default")
      (node (ref "C30") (pin "2") (pinfunction "2_2") (pintype "passive"))
      (node (ref "R22") (pin "2") (pinfunction "2_2") (pintype "passive"))
      (node (ref "U1") (pin "28") (pinfunction "AVDD_28") (pintype "power_in"))
    )
    (net (code "43") (name "Net-(U1-OSCI{slash}CLKI{slash}CN30{slash}RA2)") (class "Default")
      (node (ref "C33") (pin "2") (pinfunction "2_2") (pintype "passive"))
      (node (ref "Q1") (pin "1") (pinfunction "1_1") (pintype "passive"))
      (node (ref "U1") (pin "9") (pinfunction "OSCI/CLKI/CN30/RA2_9") (pintype "bidirectional"))
    )
    (net (code "44") (name "Net-(U1-OSCO{slash}CLKO{slash}CN29{slash}PMA0{slash}RA3)") (class "Default")
      (node (ref "C32") (pin "2") (pinfunction "2_2") (pintype "passive"))
      (node (ref "Q1") (pin "2") (pinfunction "2_2") (pintype "passive"))
      (node (ref "U1") (pin "10") (pinfunction "OSCO/CLKO/CN29/PMA0/RA3_10") (pintype "bidirectional"))
    )
    (net (code "45") (name "Net-(U1-VCAP{slash}VDDCORE)") (class "Default")
      (node (ref "C29") (pin "+") (pinfunction "+_+") (pintype "passive"))
      (node (ref "U1") (pin "20") (pinfunction "VCAP/VDDCORE_20") (pintype "power_in"))
    )
    (net (code "46") (name "Net-(U1-~{MCLR})") (class "Default")
      (node (ref "R21") (pin "1") (pinfunction "1_1") (pintype "passive"))
      (node (ref "R34") (pin "1") (pinfunction "1_1") (pintype "passive"))
      (node (ref "U1") (pin "1") (pinfunction "~{MCLR}_1") (pintype "input"))
    )
    (net (code "47") (name "Net-(U2-FILT+)") (class "Default")
      (node (ref "C22") (pin "2") (pinfunction "2_2") (pintype "passive"))
      (node (ref "C23") (pin "+") (pinfunction "+_+") (pintype "passive"))
      (node (ref "U2") (pin "22") (pinfunction "FILT+_22") (pintype "bidirectional"))
    )
    (net (code "48") (name "Net-(U2-XTI)") (class "Default")
      (node (ref "C34") (pin "1") (pinfunction "1_1") (pintype "passive"))
      (node (ref "Q2") (pin "2") (pinfunction "2_2") (pintype "passive"))
      (node (ref "U2") (pin "2") (pinfunction "XTI_2") (pintype "bidirectional"))
    )
    (net (code "49") (name "Net-(U2-XTO)") (class "Default")
      (node (ref "C35") (pin "1") (pinfunction "1_1") (pintype "passive"))
      (node (ref "Q2") (pin "1") (pinfunction "1_1") (pintype "passive"))
      (node (ref "U2") (pin "1") (pinfunction "XTO_1") (pintype "bidirectional"))
    )
    (net (code "50") (name "Net-(U7--OUT)") (class "Default")
      (node (ref "C4") (pin "-") (pinfunction "-_-") (pintype "passive"))
      (node (ref "U7") (pin "5") (pinfunction "-OUT_5") (pintype "input"))
    )
    (net (code "51") (name "Net-(U7-IN-)") (class "Default")
      (node (ref "C3") (pin "2") (pinfunction "2_2") (pintype "passive"))
      (node (ref "U7") (pin "1") (pinfunction "IN-_1") (pintype "input"))
      (node (ref "U7") (pin "3") (pinfunction "VCOM_3") (pintype "input"))
    )
    (net (code "52") (name "Net-(U8A-+IN)") (class "Default")
      (node (ref "C26") (pin "1") (pinfunction "1_1") (pintype "passive"))
      (node (ref "R17") (pin "1") (pinfunction "1_1") (pintype "passive"))
      (node (ref "U8") (pin "3") (pinfunction "+IN_3") (pintype "input"))
    )
    (net (code "53") (name "Net-(U8A--IN)") (class "Default")
      (node (ref "C36") (pin "2") (pinfunction "2_2") (pintype "passive"))
      (node (ref "C50") (pin "2") (pinfunction "2_2") (pintype "passive"))
      (node (ref "U8") (pin "1") (pinfunction "OUT_1") (pintype "output"))
      (node (ref "U8") (pin "2") (pinfunction "-IN_2") (pintype "input"))
    )
    (net (code "54") (name "Net-(U8B-+IN)") (class "Default")
      (node (ref "R19") (pin "2") (pinfunction "2_2") (pintype "passive"))
      (node (ref "U8") (pin "5") (pinfunction "+IN_5") (pintype "input"))
    )
    (net (code "55") (name "Net-(U8B--IN)") (class "Default")
      (node (ref "R18") (pin "1") (pinfunction "1_1") (pintype "passive"))
      (node (ref "R20") (pin "1") (pinfunction "1_1") (pintype "passive"))
      (node (ref "U8") (pin "6") (pinfunction "-IN_6") (pintype "input"))
    )
    (net (code "56") (name "Net-(U8B-OUT)") (class "Default")
      (node (ref "C45") (pin "2") (pinfunction "2_2") (pintype "passive"))
      (node (ref "R20") (pin "2") (pinfunction "2_2") (pintype "passive"))
      (node (ref "U8") (pin "7") (pinfunction "OUT_7") (pintype "output"))
    )
    (net (code "57") (name "Net-(U9A-+IN)") (class "Default")
      (node (ref "C4") (pin "+") (pinfunction "+_+") (pintype "passive"))
      (node (ref "R4") (pin "2") (pinfunction "2_2") (pintype "passive"))
      (node (ref "U9") (pin "3") (pinfunction "+IN_3") (pintype "input"))
    )
    (net (code "58") (name "Net-(U9A--IN)") (class "Default")
      (node (ref "C7") (pin "1") (pinfunction "1_1") (pintype "passive"))
      (node (ref "R7") (pin "2") (pinfunction "2_2") (pintype "passive"))
      (node (ref "U9") (pin "2") (pinfunction "-IN_2") (pintype "input"))
    )
    (net (code "59") (name "Net-(U9A-OUT)") (class "Default")
      (node (ref "C7") (pin "2") (pinfunction "2_2") (pintype "passive"))
      (node (ref "R5") (pin "2") (pinfunction "2_2") (pintype "passive"))
      (node (ref "U9") (pin "1") (pinfunction "OUT_1") (pintype "output"))
    )
    (net (code "60") (name "Net-(U9B-+IN)") (class "Default")
      (node (ref "C5") (pin "+") (pinfunction "+_+") (pintype "passive"))
      (node (ref "R3") (pin "2") (pinfunction "2_2") (pintype "passive"))
      (node (ref "U9") (pin "5") (pinfunction "+IN_5") (pintype "input"))
    )
    (net (code "61") (name "Net-(U9B--IN)") (class "Default")
      (node (ref "C8") (pin "1") (pinfunction "1_1") (pintype "passive"))
      (node (ref "R8") (pin "2") (pinfunction "2_2") (pintype "passive"))
      (node (ref "U9") (pin "6") (pinfunction "-IN_6") (pintype "input"))
    )
    (net (code "62") (name "Net-(U9B-OUT)") (class "Default")
      (node (ref "C8") (pin "2") (pinfunction "2_2") (pintype "passive"))
      (node (ref "R6") (pin "2") (pinfunction "2_2") (pintype "passive"))
      (node (ref "U9") (pin "7") (pinfunction "OUT_7") (pintype "output"))
    )
    (net (code "63") (name "Net-(U10A-+IN)") (class "Default")
      (node (ref "C45") (pin "1") (pinfunction "1_1") (pintype "passive"))
      (node (ref "U10") (pin "3") (pinfunction "+IN_3") (pintype "input"))
    )
    (net (code "64") (name "Net-(U10A--IN)") (class "Default")
      (node (ref "C5") (pin "-") (pinfunction "-_-") (pintype "passive"))
      (node (ref "U10") (pin "2") (pinfunction "-IN_2") (pintype "input"))
      (node (ref "U7") (pin "4") (pinfunction "+OUT_4") (pintype "output"))
    )
    (net (code "65") (name "Net-(U10A-OUT)") (class "Default")
      (node (ref "U10") (pin "6") (pinfunction "OUT_6") (pintype "output"))
      (node (ref "U7") (pin "8") (pinfunction "IN+_8") (pintype "input"))
    )
    (net (code "66") (name "Net-(U11-W)") (class "Default")
      (node (ref "C21") (pin "2") (pinfunction "2_2") (pintype "passive"))
      (node (ref "U11") (pin "5") (pinfunction "W_5") (pintype "bidirectional"))
    )
    (net (code "67") (name "Net-(U12A-+IN)") (class "Default")
      (node (ref "C17") (pin "1") (pinfunction "1_1") (pintype "passive"))
      (node (ref "R12") (pin "1") (pinfunction "1_1") (pintype "passive"))
      (node (ref "U12") (pin "3") (pinfunction "+IN_3") (pintype "input"))
    )
    (net (code "68") (name "Net-(U12A--IN)") (class "Default")
      (node (ref "C15") (pin "1") (pinfunction "1_1") (pintype "passive"))
      (node (ref "R11") (pin "1") (pinfunction "1_1") (pintype "passive"))
      (node (ref "U12") (pin "2") (pinfunction "-IN_2") (pintype "input"))
    )
    (net (code "69") (name "Net-(U12A-OUT)") (class "Default")
      (node (ref "C15") (pin "2") (pinfunction "2_2") (pintype "passive"))
      (node (ref "C16") (pin "+") (pinfunction "+_+") (pintype "passive"))
      (node (ref "R14") (pin "1") (pinfunction "1_1") (pintype "passive"))
      (node (ref "U12") (pin "1") (pinfunction "OUT_1") (pintype "output"))
    )
    (net (code "70") (name "Net-(U12B-+IN)") (class "Default")
      (node (ref "R39") (pin "2") (pinfunction "2_2") (pintype "passive"))
      (node (ref "U12") (pin "5") (pinfunction "+IN_5") (pintype "input"))
    )
    (net (code "71") (name "Net-(U12B--IN)") (class "Default")
      (node (ref "R15") (pin "1") (pinfunction "1_1") (pintype "passive"))
      (node (ref "R16") (pin "1") (pinfunction "1_1") (pintype "passive"))
      (node (ref "R38") (pin "2") (pinfunction "2_2") (pintype "passive"))
      (node (ref "U12") (pin "6") (pinfunction "-IN_6") (pintype "input"))
    )
    (net (code "72") (name "Net-(U12B-OUT)") (class "Default")
      (node (ref "C38") (pin "1") (pinfunction "1_1") (pintype "passive"))
      (node (ref "R38") (pin "1") (pinfunction "1_1") (pintype "passive"))
      (node (ref "U12") (pin "7") (pinfunction "OUT_7") (pintype "output"))
    )
    (net (code "73") (name "RELAY_CTRL") (class "Default")
      (node (ref "CTRL") (pin "1") (pinfunction "P_1") (pintype "passive"))
      (node (ref "Q4") (pin "2") (pinfunction "S_2") (pintype "passive"))
      (node (ref "R30") (pin "2") (pinfunction "2_2") (pintype "passive"))
    )
    (net (code "74") (name "SCL1") (class "Default")
      (node (ref "SCL1") (pin "1") (pinfunction "P_1") (pintype "passive"))
      (node (ref "U11") (pin "3") (pinfunction "SCL_3") (pintype "bidirectional"))
    )
    (net (code "75") (name "SDA1") (class "Default")
      (node (ref "SDA1") (pin "1") (pinfunction "P_1") (pintype "passive"))
      (node (ref "U11") (pin "4") (pinfunction "SDA_4") (pintype "bidirectional"))
    )
    (net (code "76") (name "SPI_SCL") (class "Default")
      (node (ref "U1") (pin "5") (pinfunction "PGC1/EMUC1/AN3/C2IN+/RP1/CN5/RB1_5") (pintype "bidirectional"))
      (node (ref "U3") (pin "6") (pinfunction "SCK_6") (pintype "bidirectional"))
      (node (ref "U4") (pin "6") (pinfunction "SCK_6") (pintype "bidirectional"))
      (node (ref "U5") (pin "6") (pinfunction "SCK_6") (pintype "bidirectional"))
      (node (ref "U6") (pin "6") (pinfunction "SCK_6") (pintype "bidirectional"))
    )
    (net (code "77") (name "SPI_SDI") (class "Default")
      (node (ref "U1") (pin "6") (pinfunction "AN4/C1IN-/RP2/CN6/RB2_6") (pintype "bidirectional"))
      (node (ref "U3") (pin "2") (pinfunction "SO/SIO1_2") (pintype "bidirectional"))
      (node (ref "U4") (pin "2") (pinfunction "SO/SIO1_2") (pintype "bidirectional"))
      (node (ref "U5") (pin "2") (pinfunction "SO/SIO1_2") (pintype "bidirectional"))
      (node (ref "U6") (pin "2") (pinfunction "SO/SIO1_2") (pintype "bidirectional"))
    )
    (net (code "78") (name "SPI_SDO") (class "Default")
      (node (ref "U1") (pin "4") (pinfunction "PGD1/EMUD1/AN2/C2IN-/RP0/CN4/RB0_4") (pintype "bidirectional"))
      (node (ref "U3") (pin "5") (pinfunction "SI/SIO0_5") (pintype "bidirectional"))
      (node (ref "U4") (pin "5") (pinfunction "SI/SIO0_5") (pintype "bidirectional"))
      (node (ref "U5") (pin "5") (pinfunction "SI/SIO0_5") (pintype "bidirectional"))
      (node (ref "U6") (pin "5") (pinfunction "SI/SIO0_5") (pintype "bidirectional"))
    )
    (net (code "79") (name "THRU") (class "Default")
      (node (ref "R_1") (pin "P$4") (pinfunction "3_P$4") (pintype "passive"))
      (node (ref "R_1") (pin "P$7") (pinfunction "3_P$7") (pintype "passive"))
    )
    (net (code "80") (name "V+") (class "Default")
      (node (ref "+9V") (pin "1") (pinfunction "P_1") (pintype "passive"))
      (node (ref "C2") (pin "1") (pinfunction "1_1") (pintype "passive"))
      (node (ref "C27") (pin "1") (pinfunction "1_1") (pintype "passive"))
      (node (ref "C39") (pin "1") (pinfunction "1_1") (pintype "passive"))
      (node (ref "C43") (pin "+") (pinfunction "+_+") (pintype "passive"))
      (node (ref "R36") (pin "2") (pinfunction "2_2") (pintype "passive"))
      (node (ref "U12") (pin "8") (pinfunction "V+_8") (pintype "power_in"))
      (node (ref "U13") (pin "1") (pinfunction "VI_1") (pintype "input"))
      (node (ref "U14") (pin "1") (pinfunction "VI_1") (pintype "input"))
      (node (ref "U15") (pin "3") (pinfunction "IN_3") (pintype "bidirectional"))
      (node (ref "U16") (pin "3") (pinfunction "IN_3") (pintype "bidirectional"))
      (node (ref "U8") (pin "8") (pinfunction "V+_8") (pintype "power_in"))
      (node (ref "U9") (pin "8") (pinfunction "V+_8") (pintype "power_in"))
    )
    (net (code "81") (name "VCOM") (class "Default")
      (node (ref "C11") (pin "2") (pinfunction "2_2") (pintype "passive"))
      (node (ref "C6") (pin "+") (pinfunction "+_+") (pintype "passive"))
      (node (ref "C9") (pin "2") (pinfunction "2_2") (pintype "passive"))
      (node (ref "R3") (pin "1") (pinfunction "1_1") (pintype "passive"))
      (node (ref "R4") (pin "1") (pinfunction "1_1") (pintype "passive"))
      (node (ref "U2") (pin "15") (pinfunction "VCOM_15") (pintype "bidirectional"))
    )
    (net (code "82") (name "VREF") (class "Default")
      (node (ref "C37") (pin "+") (pinfunction "+_+") (pintype "passive"))
      (node (ref "R17") (pin "2") (pinfunction "2_2") (pintype "passive"))
      (node (ref "R19") (pin "1") (pinfunction "1_1") (pintype "passive"))
      (node (ref "R2") (pin "2") (pinfunction "2_2") (pintype "passive"))
      (node (ref "R26") (pin "2") (pinfunction "2_2") (pintype "passive"))
      (node (ref "R36") (pin "1") (pinfunction "1_1") (pintype "passive"))
      (node (ref "R37") (pin "1") (pinfunction "1_1") (pintype "passive"))
      (node (ref "R39") (pin "1") (pinfunction "1_1") (pintype "passive"))
    )
    (net (code "83") (name "unconnected-(ICSP-Pad6)") (class "Default")
      (node (ref "ICSP") (pin "6") (pinfunction "6_6") (pintype "passive"))
    )
    (net (code "84") (name "unconnected-(INPUT-R-PadP$2)") (class "Default")
      (node (ref "INPUT") (pin "P$2") (pinfunction "R_P$2") (pintype "passive"))
    )
    (net (code "85") (name "unconnected-(OUTPUT-R-PadP$2)") (class "Default")
      (node (ref "OUTPUT") (pin "P$2") (pinfunction "R_P$2") (pintype "passive"))
    )
    (net (code "86") (name "unconnected-(U1-AN0{slash}VREF+{slash}CN2{slash}RA0-Pad2)") (class "Default")
      (node (ref "U1") (pin "2") (pinfunction "AN0/VREF+/CN2/RA0_2") (pintype "bidirectional"))
    )
    (net (code "87") (name "unconnected-(U1-AN1{slash}VREF-{slash}CN3{slash}RA1-Pad3)") (class "Default")
      (node (ref "U1") (pin "3") (pinfunction "AN1/VREF-/CN3/RA1_3") (pintype "bidirectional"))
    )
    (net (code "88") (name "unconnected-(U1-INT0{slash}RP7{slash}CN23{slash}PMD5{slash}RB7-Pad16)") (class "Default")
      (node (ref "U1") (pin "16") (pinfunction "INT0/RP7/CN23/PMD5/RB7_16") (pintype "bidirectional"))
    )
    (net (code "89") (name "unconnected-(U2-AINB+-Pad18)") (class "Default")
      (node (ref "U2") (pin "18") (pinfunction "AINB+_18") (pintype "bidirectional"))
    )
    (net (code "90") (name "unconnected-(U2-AINB--Pad19)") (class "Default")
      (node (ref "U2") (pin "19") (pinfunction "AINB-_19") (pintype "bidirectional"))
    )
    (net (code "91") (name "unconnected-(U2-AOUTB+-Pad26)") (class "Default")
      (node (ref "U2") (pin "26") (pinfunction "AOUTB+_26") (pintype "bidirectional"))
    )
    (net (code "92") (name "unconnected-(U2-AOUTB--Pad27)") (class "Default")
      (node (ref "U2") (pin "27") (pinfunction "AOUTB-_27") (pintype "bidirectional"))
    )
    (net (code "93") (name "unconnected-(U2-MCLK-Pad3)") (class "Default")
      (node (ref "U2") (pin "3") (pinfunction "MCLK_3") (pintype "bidirectional"))
    )
    (net (code "94") (name "unconnected-(U2-~{AMUTEC}-Pad23)") (class "Default")
      (node (ref "U2") (pin "23") (pinfunction "~{AMUTEC}_23") (pintype "bidirectional"))
    )
    (net (code "95") (name "unconnected-(U2-~{BMUTEC}-Pad28)") (class "Default")
      (node (ref "U2") (pin "28") (pinfunction "~{BMUTEC}_28") (pintype "bidirectional"))
    )
    (net (code "96") (name "unconnected-(U3-NC-Pad3)") (class "Default")
      (node (ref "U3") (pin "3") (pinfunction "NC_3") (pintype "bidirectional"))
    )
    (net (code "97") (name "unconnected-(U3-VBAT-Pad7)") (class "Default")
      (node (ref "U3") (pin "7") (pinfunction "VBAT_7") (pintype "bidirectional"))
    )
    (net (code "98") (name "unconnected-(U4-NC-Pad3)") (class "Default")
      (node (ref "U4") (pin "3") (pinfunction "NC_3") (pintype "bidirectional"))
    )
    (net (code "99") (name "unconnected-(U4-VBAT-Pad7)") (class "Default")
      (node (ref "U4") (pin "7") (pinfunction "VBAT_7") (pintype "bidirectional"))
    )
    (net (code "100") (name "unconnected-(U5-NC-Pad3)") (class "Default")
      (node (ref "U5") (pin "3") (pinfunction "NC_3") (pintype "bidirectional"))
    )
    (net (code "101") (name "unconnected-(U5-VBAT-Pad7)") (class "Default")
      (node (ref "U5") (pin "7") (pinfunction "VBAT_7") (pintype "bidirectional"))
    )
    (net (code "102") (name "unconnected-(U6-NC-Pad3)") (class "Default")
      (node (ref "U6") (pin "3") (pinfunction "NC_3") (pintype "bidirectional"))
    )
    (net (code "103") (name "unconnected-(U6-VBAT-Pad7)") (class "Default")
      (node (ref "U6") (pin "7") (pinfunction "VBAT_7") (pintype "bidirectional"))
    )
    (net (code "104") (name "unconnected-(U7-NC-Pad6)") (class "Default")
      (node (ref "U7") (pin "6") (pinfunction "NC_6") (pintype "no_connect"))
    )
    (net (code "105") (name "unconnected-(X1-P-Pad1)") (class "Default")
      (node (ref "X1") (pin "1") (pinfunction "P_1") (pintype "passive"))
    )
    (net (code "106") (name "~{CS0}") (class "Default")
      (node (ref "R25") (pin "1") (pinfunction "1_1") (pintype "passive"))
      (node (ref "U1") (pin "7") (pinfunction "AN5/C1IN+/RP3/CN7/RB3_7") (pintype "bidirectional"))
      (node (ref "U3") (pin "1") (pinfunction "~{CS}_1") (pintype "bidirectional"))
    )
    (net (code "107") (name "~{CS1}") (class "Default")
      (node (ref "R24") (pin "1") (pinfunction "1_1") (pintype "passive"))
      (node (ref "U1") (pin "14") (pinfunction "PGD3/EMUD3/ASDA1/RP5/CN27/PMD7/RB5_14") (pintype "bidirectional"))
      (node (ref "U4") (pin "1") (pinfunction "~{CS}_1") (pintype "bidirectional"))
    )
    (net (code "108") (name "~{CS2}") (class "Default")
      (node (ref "R23") (pin "1") (pinfunction "1_1") (pintype "passive"))
      (node (ref "U1") (pin "12") (pinfunction "SOSCO/T1CK/CN0/PMA1/RA4_12") (pintype "bidirectional"))
      (node (ref "U5") (pin "1") (pinfunction "~{CS}_1") (pintype "bidirectional"))
    )
    (net (code "109") (name "~{CS3}") (class "Default")
      (node (ref "R28") (pin "1") (pinfunction "1_1") (pintype "passive"))
      (node (ref "U1") (pin "11") (pinfunction "SOSCI/RP4/CN1/PMBE/RB4_11") (pintype "bidirectional"))
      (node (ref "U6") (pin "1") (pinfunction "~{CS}_1") (pintype "bidirectional"))
    )
    (net (code "110") (name "~{MCLR}") (class "Default")
      (node (ref "ICSP") (pin "1") (pinfunction "1_1") (pintype "passive"))
      (node (ref "R34") (pin "2") (pinfunction "2_2") (pintype "passive"))
    )
  )
)
